# Sensor_PCI_Sch_V2.net
KiCad netlist of a schematic drawn in Altium Designer
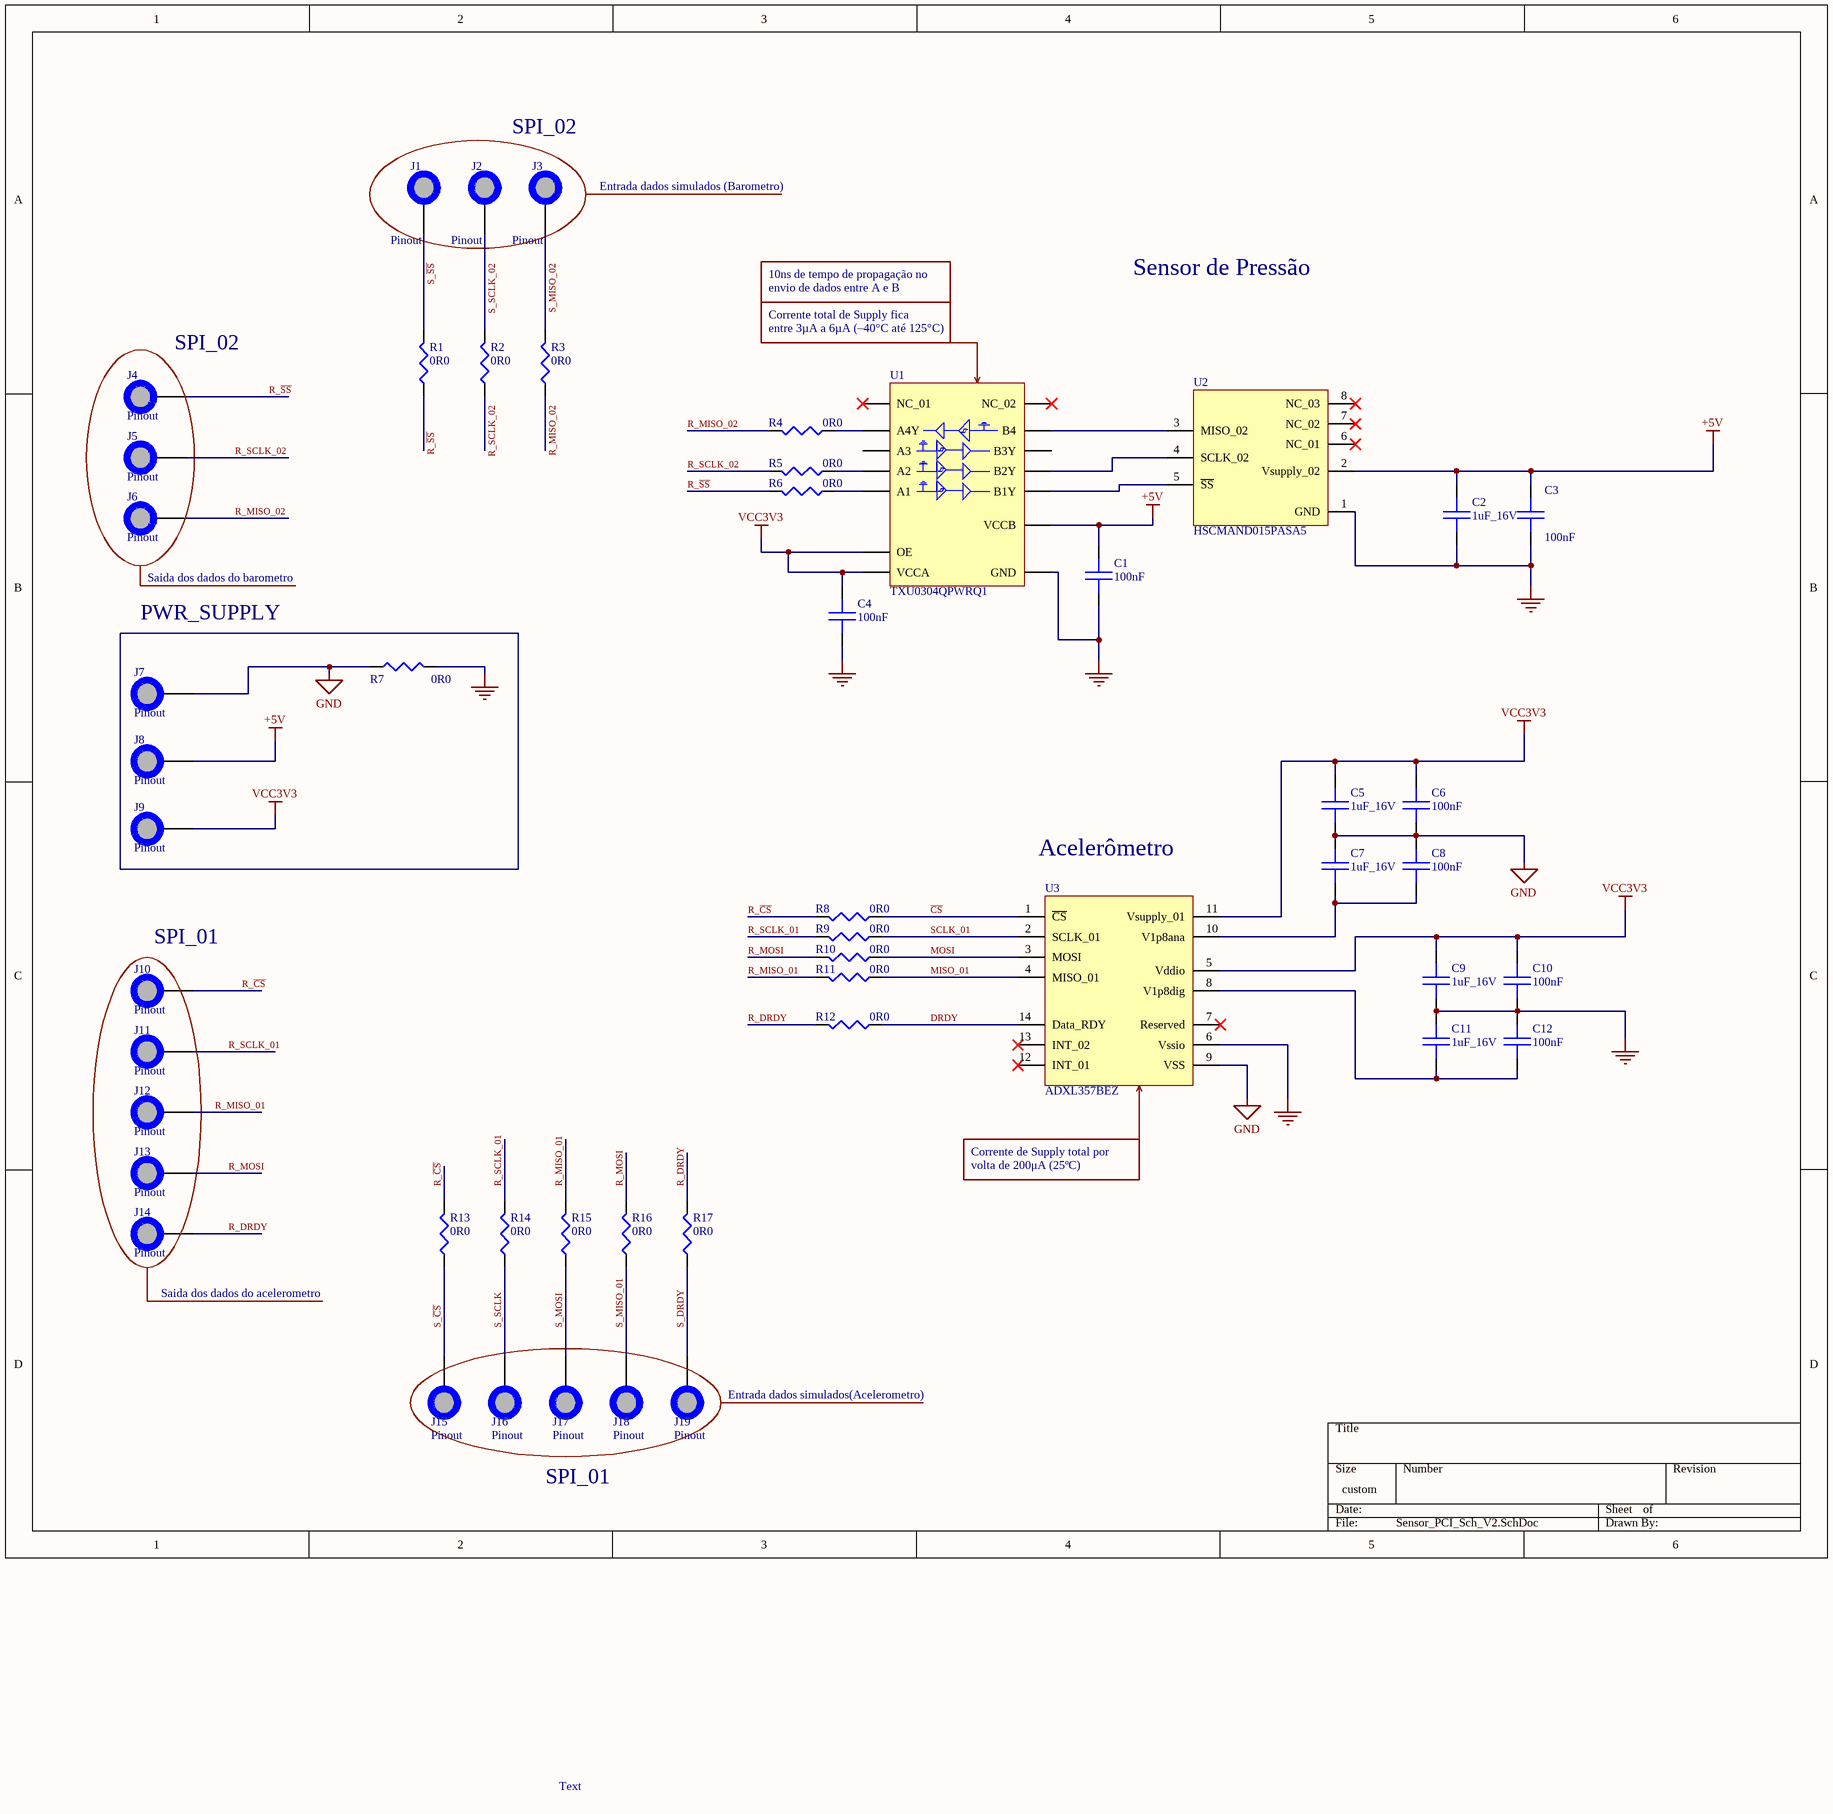
[diagram p0: Sensor_PCI_Sch_V2.SchDoc]

(export (version "E")
  (design (tool "Eeschema 10.0.6"))
  (components
    (comp (ref "C1")
      (value "100nF")
      (footprint "CP_0805")
      (description "Cap Ceramic 0.1uF 50V X7R 20% Pad SMD 0805 150°C T/R")
      (fields
        (field (name "MANUFACTURER") "Vishay Vitramon")
        (field (name "MANUFACTURER PART NUMBER") "VJ0805Y104MXAMR")
      )
      (libsource (lib "Sensor_PCI_schlib") (part "C_0805_0.1uF"))
    )
    (comp (ref "C2")
      (value "1uF_16V")
      (footprint "C_1206")
      (description "Cap Ceramic 1uF 16V Y5V 20% SMD 1206 85°C Plastic T/R")
      (fields
        (field (name "MANUFACTURER") "Vishay Vitramon")
        (field (name "MANUFACTURER PART NUMBER") "VJ1206V105MXJTW1BC")
      )
      (libsource (lib "Sensor_PCI_schlib") (part "C_1206_1uF_16V"))
    )
    (comp (ref "C3")
      (value "100nF")
      (footprint "CP_0805")
      (description "Cap Ceramic 0.1uF 50V X7R 20% Pad SMD 0805 150°C T/R")
      (fields
        (field (name "MANUFACTURER") "Vishay Vitramon")
        (field (name "MANUFACTURER PART NUMBER") "VJ0805Y104MXAMR")
      )
      (libsource (lib "Sensor_PCI_schlib") (part "C_0805_0.1uF"))
    )
    (comp (ref "C4")
      (value "100nF")
      (footprint "CP_0805")
      (description "Cap Ceramic 0.1uF 50V X7R 20% Pad SMD 0805 150°C T/R")
      (fields
        (field (name "MANUFACTURER") "Vishay Vitramon")
        (field (name "MANUFACTURER PART NUMBER") "VJ0805Y104MXAMR")
      )
      (libsource (lib "Sensor_PCI_schlib") (part "C_0805_0.1uF"))
    )
    (comp (ref "C5")
      (value "1uF_16V")
      (footprint "C_1206")
      (description "Cap Ceramic 1uF 16V Y5V 20% SMD 1206 85°C Plastic T/R")
      (fields
        (field (name "MANUFACTURER") "Vishay Vitramon")
        (field (name "MANUFACTURER PART NUMBER") "VJ1206V105MXJTW1BC")
      )
      (libsource (lib "Sensor_PCI_schlib") (part "C_1206_1uF_16V"))
    )
    (comp (ref "C6")
      (value "100nF")
      (footprint "CP_0805")
      (description "Cap Ceramic 0.1uF 50V X7R 20% Pad SMD 0805 150°C T/R")
      (fields
        (field (name "MANUFACTURER") "Vishay Vitramon")
        (field (name "MANUFACTURER PART NUMBER") "VJ0805Y104MXAMR")
      )
      (libsource (lib "Sensor_PCI_schlib") (part "C_0805_0.1uF"))
    )
    (comp (ref "C7")
      (value "1uF_16V")
      (footprint "C_1206")
      (description "Cap Ceramic 1uF 16V Y5V 20% SMD 1206 85°C Plastic T/R")
      (fields
        (field (name "MANUFACTURER") "Vishay Vitramon")
        (field (name "MANUFACTURER PART NUMBER") "VJ1206V105MXJTW1BC")
      )
      (libsource (lib "Sensor_PCI_schlib") (part "C_1206_1uF_16V"))
    )
    (comp (ref "C8")
      (value "100nF")
      (footprint "CP_0805")
      (description "Cap Ceramic 0.1uF 50V X7R 20% Pad SMD 0805 150°C T/R")
      (fields
        (field (name "MANUFACTURER") "Vishay Vitramon")
        (field (name "MANUFACTURER PART NUMBER") "VJ0805Y104MXAMR")
      )
      (libsource (lib "Sensor_PCI_schlib") (part "C_0805_0.1uF"))
    )
    (comp (ref "C9")
      (value "1uF_16V")
      (footprint "C_1206")
      (description "Cap Ceramic 1uF 16V Y5V 20% SMD 1206 85°C Plastic T/R")
      (fields
        (field (name "MANUFACTURER") "Vishay Vitramon")
        (field (name "MANUFACTURER PART NUMBER") "VJ1206V105MXJTW1BC")
      )
      (libsource (lib "Sensor_PCI_schlib") (part "C_1206_1uF_16V"))
    )
    (comp (ref "C10")
      (value "100nF")
      (footprint "CP_0805")
      (description "Cap Ceramic 0.1uF 50V X7R 20% Pad SMD 0805 150°C T/R")
      (fields
        (field (name "MANUFACTURER") "Vishay Vitramon")
        (field (name "MANUFACTURER PART NUMBER") "VJ0805Y104MXAMR")
      )
      (libsource (lib "Sensor_PCI_schlib") (part "C_0805_0.1uF"))
    )
    (comp (ref "C11")
      (value "1uF_16V")
      (footprint "C_1206")
      (description "Cap Ceramic 1uF 16V Y5V 20% SMD 1206 85°C Plastic T/R")
      (fields
        (field (name "MANUFACTURER") "Vishay Vitramon")
        (field (name "MANUFACTURER PART NUMBER") "VJ1206V105MXJTW1BC")
      )
      (libsource (lib "Sensor_PCI_schlib") (part "C_1206_1uF_16V"))
    )
    (comp (ref "C12")
      (value "100nF")
      (footprint "CP_0805")
      (description "Cap Ceramic 0.1uF 50V X7R 20% Pad SMD 0805 150°C T/R")
      (fields
        (field (name "MANUFACTURER") "Vishay Vitramon")
        (field (name "MANUFACTURER PART NUMBER") "VJ0805Y104MXAMR")
      )
      (libsource (lib "Sensor_PCI_schlib") (part "C_0805_0.1uF"))
    )
    (comp (ref "J1")
      (value "Pinout")
      (footprint "Pinout")
      (libsource (lib "Sensor_PCI_schlib") (part "Pinout"))
    )
    (comp (ref "J2")
      (value "Pinout")
      (footprint "Pinout")
      (libsource (lib "Sensor_PCI_schlib") (part "Pinout"))
    )
    (comp (ref "J3")
      (value "Pinout")
      (footprint "Pinout")
      (libsource (lib "Sensor_PCI_schlib") (part "Pinout"))
    )
    (comp (ref "J4")
      (value "Pinout")
      (footprint "Pinout")
      (libsource (lib "Sensor_PCI_schlib") (part "Pinout"))
    )
    (comp (ref "J5")
      (value "Pinout")
      (footprint "Pinout")
      (libsource (lib "Sensor_PCI_schlib") (part "Pinout"))
    )
    (comp (ref "J6")
      (value "Pinout")
      (footprint "Pinout")
      (libsource (lib "Sensor_PCI_schlib") (part "Pinout"))
    )
    (comp (ref "J7")
      (value "Pinout")
      (footprint "Pinout")
      (libsource (lib "Sensor_PCI_schlib") (part "Pinout"))
    )
    (comp (ref "J8")
      (value "Pinout")
      (footprint "Pinout")
      (libsource (lib "Sensor_PCI_schlib") (part "Pinout"))
    )
    (comp (ref "J9")
      (value "Pinout")
      (footprint "Pinout")
      (libsource (lib "Sensor_PCI_schlib") (part "Pinout"))
    )
    (comp (ref "J10")
      (value "Pinout")
      (footprint "Pinout")
      (libsource (lib "Sensor_PCI_schlib") (part "Pinout"))
    )
    (comp (ref "J11")
      (value "Pinout")
      (footprint "Pinout")
      (libsource (lib "Sensor_PCI_schlib") (part "Pinout"))
    )
    (comp (ref "J12")
      (value "Pinout")
      (footprint "Pinout")
      (libsource (lib "Sensor_PCI_schlib") (part "Pinout"))
    )
    (comp (ref "J13")
      (value "Pinout")
      (footprint "Pinout")
      (libsource (lib "Sensor_PCI_schlib") (part "Pinout"))
    )
    (comp (ref "J14")
      (value "Pinout")
      (footprint "Pinout")
      (libsource (lib "Sensor_PCI_schlib") (part "Pinout"))
    )
    (comp (ref "J15")
      (value "Pinout")
      (footprint "Pinout")
      (libsource (lib "Sensor_PCI_schlib") (part "Pinout"))
    )
    (comp (ref "J16")
      (value "Pinout")
      (footprint "Pinout")
      (libsource (lib "Sensor_PCI_schlib") (part "Pinout"))
    )
    (comp (ref "J17")
      (value "Pinout")
      (footprint "Pinout")
      (libsource (lib "Sensor_PCI_schlib") (part "Pinout"))
    )
    (comp (ref "J18")
      (value "Pinout")
      (footprint "Pinout")
      (libsource (lib "Sensor_PCI_schlib") (part "Pinout"))
    )
    (comp (ref "J19")
      (value "Pinout")
      (footprint "Pinout")
      (libsource (lib "Sensor_PCI_schlib") (part "Pinout"))
    )
    (comp (ref "R1")
      (value "0R0")
      (footprint "R_0805")
      (description "CRCW Thick Film Commodity Chip Resistor Jumper 0805 Size 0 Ohm 0.125 W 2-Pin SMD Paper T/R")
      (fields
        (field (name "MANUFACTURER") "Vishay Dale")
        (field (name "MANUFACTURER PART NUMBER") "CRCW08050000Z0ECC")
      )
      (libsource (lib "Sensor_PCI_schlib") (part "Res_0805_0R0"))
    )
    (comp (ref "R2")
      (value "0R0")
      (footprint "R_0805")
      (description "CRCW Thick Film Commodity Chip Resistor Jumper 0805 Size 0 Ohm 0.125 W 2-Pin SMD Paper T/R")
      (fields
        (field (name "MANUFACTURER") "Vishay Dale")
        (field (name "MANUFACTURER PART NUMBER") "CRCW08050000Z0ECC")
      )
      (libsource (lib "Sensor_PCI_schlib") (part "Res_0805_0R0"))
    )
    (comp (ref "R3")
      (value "0R0")
      (footprint "R_0805")
      (description "CRCW Thick Film Commodity Chip Resistor Jumper 0805 Size 0 Ohm 0.125 W 2-Pin SMD Paper T/R")
      (fields
        (field (name "MANUFACTURER") "Vishay Dale")
        (field (name "MANUFACTURER PART NUMBER") "CRCW08050000Z0ECC")
      )
      (libsource (lib "Sensor_PCI_schlib") (part "Res_0805_0R0"))
    )
    (comp (ref "R4")
      (value "0R0")
      (footprint "R_0805")
      (description "CRCW Thick Film Commodity Chip Resistor Jumper 0805 Size 0 Ohm 0.125 W 2-Pin SMD Paper T/R")
      (fields
        (field (name "MANUFACTURER") "Vishay Dale")
        (field (name "MANUFACTURER PART NUMBER") "CRCW08050000Z0ECC")
      )
      (libsource (lib "Sensor_PCI_schlib") (part "Res_0805_0R0"))
    )
    (comp (ref "R5")
      (value "0R0")
      (footprint "R_0805")
      (description "CRCW Thick Film Commodity Chip Resistor Jumper 0805 Size 0 Ohm 0.125 W 2-Pin SMD Paper T/R")
      (fields
        (field (name "MANUFACTURER") "Vishay Dale")
        (field (name "MANUFACTURER PART NUMBER") "CRCW08050000Z0ECC")
      )
      (libsource (lib "Sensor_PCI_schlib") (part "Res_0805_0R0"))
    )
    (comp (ref "R6")
      (value "0R0")
      (footprint "R_0805")
      (description "CRCW Thick Film Commodity Chip Resistor Jumper 0805 Size 0 Ohm 0.125 W 2-Pin SMD Paper T/R")
      (fields
        (field (name "MANUFACTURER") "Vishay Dale")
        (field (name "MANUFACTURER PART NUMBER") "CRCW08050000Z0ECC")
      )
      (libsource (lib "Sensor_PCI_schlib") (part "Res_0805_0R0"))
    )
    (comp (ref "R7")
      (value "0R0")
      (footprint "R_0805")
      (description "CRCW Thick Film Commodity Chip Resistor Jumper 0805 Size 0 Ohm 0.125 W 2-Pin SMD Paper T/R")
      (fields
        (field (name "MANUFACTURER") "Vishay Dale")
        (field (name "MANUFACTURER PART NUMBER") "CRCW08050000Z0ECC")
      )
      (libsource (lib "Sensor_PCI_schlib") (part "Res_0805_0R0"))
    )
    (comp (ref "R8")
      (value "0R0")
      (footprint "R_0805")
      (description "CRCW Thick Film Commodity Chip Resistor Jumper 0805 Size 0 Ohm 0.125 W 2-Pin SMD Paper T/R")
      (fields
        (field (name "MANUFACTURER") "Vishay Dale")
        (field (name "MANUFACTURER PART NUMBER") "CRCW08050000Z0ECC")
      )
      (libsource (lib "Sensor_PCI_schlib") (part "Res_0805_0R0"))
    )
    (comp (ref "R9")
      (value "0R0")
      (footprint "R_0805")
      (description "CRCW Thick Film Commodity Chip Resistor Jumper 0805 Size 0 Ohm 0.125 W 2-Pin SMD Paper T/R")
      (fields
        (field (name "MANUFACTURER") "Vishay Dale")
        (field (name "MANUFACTURER PART NUMBER") "CRCW08050000Z0ECC")
      )
      (libsource (lib "Sensor_PCI_schlib") (part "Res_0805_0R0"))
    )
    (comp (ref "R10")
      (value "0R0")
      (footprint "R_0805")
      (description "CRCW Thick Film Commodity Chip Resistor Jumper 0805 Size 0 Ohm 0.125 W 2-Pin SMD Paper T/R")
      (fields
        (field (name "MANUFACTURER") "Vishay Dale")
        (field (name "MANUFACTURER PART NUMBER") "CRCW08050000Z0ECC")
      )
      (libsource (lib "Sensor_PCI_schlib") (part "Res_0805_0R0"))
    )
    (comp (ref "R11")
      (value "0R0")
      (footprint "R_0805")
      (description "CRCW Thick Film Commodity Chip Resistor Jumper 0805 Size 0 Ohm 0.125 W 2-Pin SMD Paper T/R")
      (fields
        (field (name "MANUFACTURER") "Vishay Dale")
        (field (name "MANUFACTURER PART NUMBER") "CRCW08050000Z0ECC")
      )
      (libsource (lib "Sensor_PCI_schlib") (part "Res_0805_0R0"))
    )
    (comp (ref "R12")
      (value "0R0")
      (footprint "R_0805")
      (description "CRCW Thick Film Commodity Chip Resistor Jumper 0805 Size 0 Ohm 0.125 W 2-Pin SMD Paper T/R")
      (fields
        (field (name "MANUFACTURER") "Vishay Dale")
        (field (name "MANUFACTURER PART NUMBER") "CRCW08050000Z0ECC")
      )
      (libsource (lib "Sensor_PCI_schlib") (part "Res_0805_0R0"))
    )
    (comp (ref "R13")
      (value "0R0")
      (footprint "R_0805")
      (description "CRCW Thick Film Commodity Chip Resistor Jumper 0805 Size 0 Ohm 0.125 W 2-Pin SMD Paper T/R")
      (fields
        (field (name "MANUFACTURER") "Vishay Dale")
        (field (name "MANUFACTURER PART NUMBER") "CRCW08050000Z0ECC")
      )
      (libsource (lib "Sensor_PCI_schlib") (part "Res_0805_0R0"))
    )
    (comp (ref "R14")
      (value "0R0")
      (footprint "R_0805")
      (description "CRCW Thick Film Commodity Chip Resistor Jumper 0805 Size 0 Ohm 0.125 W 2-Pin SMD Paper T/R")
      (fields
        (field (name "MANUFACTURER") "Vishay Dale")
        (field (name "MANUFACTURER PART NUMBER") "CRCW08050000Z0ECC")
      )
      (libsource (lib "Sensor_PCI_schlib") (part "Res_0805_0R0"))
    )
    (comp (ref "R15")
      (value "0R0")
      (footprint "R_0805")
      (description "CRCW Thick Film Commodity Chip Resistor Jumper 0805 Size 0 Ohm 0.125 W 2-Pin SMD Paper T/R")
      (fields
        (field (name "MANUFACTURER") "Vishay Dale")
        (field (name "MANUFACTURER PART NUMBER") "CRCW08050000Z0ECC")
      )
      (libsource (lib "Sensor_PCI_schlib") (part "Res_0805_0R0"))
    )
    (comp (ref "R16")
      (value "0R0")
      (footprint "R_0805")
      (description "CRCW Thick Film Commodity Chip Resistor Jumper 0805 Size 0 Ohm 0.125 W 2-Pin SMD Paper T/R")
      (fields
        (field (name "MANUFACTURER") "Vishay Dale")
        (field (name "MANUFACTURER PART NUMBER") "CRCW08050000Z0ECC")
      )
      (libsource (lib "Sensor_PCI_schlib") (part "Res_0805_0R0"))
    )
    (comp (ref "R17")
      (value "0R0")
      (footprint "R_0805")
      (description "CRCW Thick Film Commodity Chip Resistor Jumper 0805 Size 0 Ohm 0.125 W 2-Pin SMD Paper T/R")
      (fields
        (field (name "MANUFACTURER") "Vishay Dale")
        (field (name "MANUFACTURER PART NUMBER") "CRCW08050000Z0ECC")
      )
      (libsource (lib "Sensor_PCI_schlib") (part "Res_0805_0R0"))
    )
    (comp (ref "U1")
      (value "TXU0304QPWRQ1")
      (footprint "TSSOP-PW")
      (description "Automotive four channel unidirectional level shifter 14-TSSOP -40 to 125")
      (fields (field (name "MANUFACTURER") "Texas Instruments"))
      (libsource (lib "Sensor_PCI_schlib") (part "Tradutor fixo de Tensão-SPI"))
    )
    (comp (ref "U2")
      (value "HSCMAND015PASA5")
      (footprint "SMT_08_2.54mm")
      (description "Board Mount Pressure Sensors SMT, Single Ax Barbed Absolute, 5V")
      (fields (field (name "MANUFACTURER") "Honeywell Sensing & Control"))
      (libsource (lib "Sensor_PCI_schlib") (part "Sensor_Pressão"))
    )
    (comp (ref "U3")
      (value "ADXL357BEZ")
      (footprint "Quad_14_1.2mm")
      (description "Accelerometer Tri-axis Digital Accel")
      (fields (field (name "MANUFACTURER") "Analog Devices"))
      (libsource (lib "Sensor_PCI_schlib") (part "Acelerômetro"))
    )
  )
  (nets
    (net (code "1") (name "+5V") (class "Default")
      (node (ref "C1") (pin "2") (pinfunction "2_2") (pintype "passive"))
      (node (ref "C2") (pin "1") (pinfunction "3_1") (pintype "passive"))
      (node (ref "C3") (pin "2") (pinfunction "2_2") (pintype "passive"))
      (node (ref "J8") (pin "1") (pinfunction "1_1") (pintype "passive"))
      (node (ref "U1") (pin "14") (pinfunction "VCCB_14") (pintype "passive"))
      (node (ref "U2") (pin "2") (pinfunction "Vsupply_02_2") (pintype "passive"))
    )
    (net (code "2") (name "/DRDY") (class "Default")
      (node (ref "R12") (pin "1") (pinfunction "1_1") (pintype "passive"))
      (node (ref "U3") (pin "14") (pinfunction "Data_RDY_14") (pintype "passive"))
    )
    (net (code "3") (name "/MISO_01") (class "Default")
      (node (ref "R11") (pin "1") (pinfunction "1_1") (pintype "passive"))
      (node (ref "U3") (pin "4") (pinfunction "MISO_01_4") (pintype "passive"))
    )
    (net (code "4") (name "/MOSI") (class "Default")
      (node (ref "R10") (pin "1") (pinfunction "1_1") (pintype "passive"))
      (node (ref "U3") (pin "3") (pinfunction "MOSI_3") (pintype "passive"))
    )
    (net (code "5") (name "/R_DRDY") (class "Default")
      (node (ref "J14") (pin "1") (pinfunction "1_1") (pintype "passive"))
      (node (ref "R12") (pin "2") (pinfunction "2_2") (pintype "passive"))
      (node (ref "R17") (pin "2") (pinfunction "2_2") (pintype "passive"))
    )
    (net (code "6") (name "/R_MISO_01") (class "Default")
      (node (ref "J12") (pin "1") (pinfunction "1_1") (pintype "passive"))
      (node (ref "R11") (pin "2") (pinfunction "2_2") (pintype "passive"))
      (node (ref "R15") (pin "2") (pinfunction "2_2") (pintype "passive"))
    )
    (net (code "7") (name "/R_MISO_02") (class "Default")
      (node (ref "J6") (pin "1") (pinfunction "1_1") (pintype "passive"))
      (node (ref "R3") (pin "1") (pinfunction "1_1") (pintype "passive"))
      (node (ref "R4") (pin "2") (pinfunction "2_2") (pintype "passive"))
    )
    (net (code "8") (name "/R_MOSI") (class "Default")
      (node (ref "J13") (pin "1") (pinfunction "1_1") (pintype "passive"))
      (node (ref "R10") (pin "2") (pinfunction "2_2") (pintype "passive"))
      (node (ref "R16") (pin "2") (pinfunction "2_2") (pintype "passive"))
    )
    (net (code "9") (name "/R_SCLK_01") (class "Default")
      (node (ref "J11") (pin "1") (pinfunction "1_1") (pintype "passive"))
      (node (ref "R14") (pin "2") (pinfunction "2_2") (pintype "passive"))
      (node (ref "R9") (pin "2") (pinfunction "2_2") (pintype "passive"))
    )
    (net (code "10") (name "/R_SCLK_02") (class "Default")
      (node (ref "J5") (pin "1") (pinfunction "1_1") (pintype "passive"))
      (node (ref "R2") (pin "1") (pinfunction "1_1") (pintype "passive"))
      (node (ref "R5") (pin "2") (pinfunction "2_2") (pintype "passive"))
    )
    (net (code "11") (name "/R_~{CS}") (class "Default")
      (node (ref "J10") (pin "1") (pinfunction "1_1") (pintype "passive"))
      (node (ref "R13") (pin "2") (pinfunction "2_2") (pintype "passive"))
      (node (ref "R8") (pin "2") (pinfunction "2_2") (pintype "passive"))
    )
    (net (code "12") (name "/R_~{SS}") (class "Default")
      (node (ref "J4") (pin "1") (pinfunction "1_1") (pintype "passive"))
      (node (ref "R1") (pin "1") (pinfunction "1_1") (pintype "passive"))
      (node (ref "R6") (pin "2") (pinfunction "2_2") (pintype "passive"))
    )
    (net (code "13") (name "/SCLK_01") (class "Default")
      (node (ref "R9") (pin "1") (pinfunction "1_1") (pintype "passive"))
      (node (ref "U3") (pin "2") (pinfunction "SCLK_01_2") (pintype "passive"))
    )
    (net (code "14") (name "/S_DRDY") (class "Default")
      (node (ref "J19") (pin "1") (pinfunction "1_1") (pintype "passive"))
      (node (ref "R17") (pin "1") (pinfunction "1_1") (pintype "passive"))
    )
    (net (code "15") (name "/S_MISO_01") (class "Default")
      (node (ref "J18") (pin "1") (pinfunction "1_1") (pintype "passive"))
      (node (ref "R16") (pin "1") (pinfunction "1_1") (pintype "passive"))
    )
    (net (code "16") (name "/S_MISO_02") (class "Default")
      (node (ref "J3") (pin "1") (pinfunction "1_1") (pintype "passive"))
      (node (ref "R3") (pin "2") (pinfunction "2_2") (pintype "passive"))
    )
    (net (code "17") (name "/S_MOSI") (class "Default")
      (node (ref "J17") (pin "1") (pinfunction "1_1") (pintype "passive"))
      (node (ref "R15") (pin "1") (pinfunction "1_1") (pintype "passive"))
    )
    (net (code "18") (name "/S_SCLK") (class "Default")
      (node (ref "J16") (pin "1") (pinfunction "1_1") (pintype "passive"))
      (node (ref "R14") (pin "1") (pinfunction "1_1") (pintype "passive"))
    )
    (net (code "19") (name "/S_SCLK_02") (class "Default")
      (node (ref "J2") (pin "1") (pinfunction "1_1") (pintype "passive"))
      (node (ref "R2") (pin "2") (pinfunction "2_2") (pintype "passive"))
    )
    (net (code "20") (name "/S_~{CS}") (class "Default")
      (node (ref "J15") (pin "1") (pinfunction "1_1") (pintype "passive"))
      (node (ref "R13") (pin "1") (pinfunction "1_1") (pintype "passive"))
    )
    (net (code "21") (name "/S_~{SS}") (class "Default")
      (node (ref "J1") (pin "1") (pinfunction "1_1") (pintype "passive"))
      (node (ref "R1") (pin "2") (pinfunction "2_2") (pintype "passive"))
    )
    (net (code "22") (name "/~{CS}") (class "Default")
      (node (ref "R8") (pin "1") (pinfunction "1_1") (pintype "passive"))
      (node (ref "U3") (pin "1") (pinfunction "~{CS}_1") (pintype "passive"))
    )
    (net (code "23") (name "GND") (class "Default")
      (node (ref "C1") (pin "1") (pinfunction "1_1") (pintype "passive"))
      (node (ref "C10") (pin "1") (pinfunction "1_1") (pintype "passive"))
      (node (ref "C11") (pin "1") (pinfunction "3_1") (pintype "passive"))
      (node (ref "C12") (pin "2") (pinfunction "2_2") (pintype "passive"))
      (node (ref "C2") (pin "2") (pinfunction "4_2") (pintype "passive"))
      (node (ref "C3") (pin "1") (pinfunction "1_1") (pintype "passive"))
      (node (ref "C4") (pin "1") (pinfunction "1_1") (pintype "passive"))
      (node (ref "C5") (pin "2") (pinfunction "4_2") (pintype "passive"))
      (node (ref "C6") (pin "1") (pinfunction "1_1") (pintype "passive"))
      (node (ref "C7") (pin "1") (pinfunction "3_1") (pintype "passive"))
      (node (ref "C8") (pin "2") (pinfunction "2_2") (pintype "passive"))
      (node (ref "C9") (pin "2") (pinfunction "4_2") (pintype "passive"))
      (node (ref "J7") (pin "1") (pinfunction "1_1") (pintype "passive"))
      (node (ref "R7") (pin "1") (pinfunction "1_1") (pintype "passive"))
      (node (ref "R7") (pin "2") (pinfunction "2_2") (pintype "passive"))
      (node (ref "U1") (pin "7") (pinfunction "GND_7") (pintype "passive"))
      (node (ref "U2") (pin "1") (pinfunction "GND_1") (pintype "passive"))
      (node (ref "U3") (pin "6") (pinfunction "Vssio_6") (pintype "passive"))
      (node (ref "U3") (pin "9") (pinfunction "VSS_9") (pintype "passive"))
    )
    (net (code "24") (name "Net-(C7-4)") (class "Default")
      (node (ref "C7") (pin "2") (pinfunction "4_2") (pintype "passive"))
      (node (ref "C8") (pin "1") (pinfunction "1_1") (pintype "passive"))
      (node (ref "U3") (pin "10") (pinfunction "V1p8ana_10") (pintype "passive"))
    )
    (net (code "25") (name "Net-(C11-4)") (class "Default")
      (node (ref "C11") (pin "2") (pinfunction "4_2") (pintype "passive"))
      (node (ref "C12") (pin "1") (pinfunction "1_1") (pintype "passive"))
      (node (ref "U3") (pin "8") (pinfunction "V1p8dig_8") (pintype "passive"))
    )
    (net (code "26") (name "Net-(U1-A1)") (class "Default")
      (node (ref "R6") (pin "1") (pinfunction "1_1") (pintype "passive"))
      (node (ref "U1") (pin "2") (pinfunction "A1_2") (pintype "passive"))
    )
    (net (code "27") (name "Net-(U1-A2)") (class "Default")
      (node (ref "R5") (pin "1") (pinfunction "1_1") (pintype "passive"))
      (node (ref "U1") (pin "3") (pinfunction "A2_3") (pintype "passive"))
    )
    (net (code "28") (name "Net-(U1-A4Y)") (class "Default")
      (node (ref "R4") (pin "1") (pinfunction "1_1") (pintype "passive"))
      (node (ref "U1") (pin "5") (pinfunction "A4Y_5") (pintype "passive"))
    )
    (net (code "29") (name "Net-(U1-B1Y)") (class "Default")
      (node (ref "U1") (pin "13") (pinfunction "B1Y_13") (pintype "passive"))
      (node (ref "U2") (pin "5") (pinfunction "~{SS}_5") (pintype "passive"))
    )
    (net (code "30") (name "Net-(U1-B2Y)") (class "Default")
      (node (ref "U1") (pin "12") (pinfunction "B2Y_12") (pintype "passive"))
      (node (ref "U2") (pin "4") (pinfunction "SCLK_02_4") (pintype "passive"))
    )
    (net (code "31") (name "Net-(U1-B4)") (class "Default")
      (node (ref "U1") (pin "10") (pinfunction "B4_10") (pintype "passive"))
      (node (ref "U2") (pin "3") (pinfunction "MISO_02_3") (pintype "passive"))
    )
    (net (code "32") (name "VCC3V3") (class "Default")
      (node (ref "C10") (pin "2") (pinfunction "2_2") (pintype "passive"))
      (node (ref "C4") (pin "2") (pinfunction "2_2") (pintype "passive"))
      (node (ref "C5") (pin "1") (pinfunction "3_1") (pintype "passive"))
      (node (ref "C6") (pin "2") (pinfunction "2_2") (pintype "passive"))
      (node (ref "C9") (pin "1") (pinfunction "3_1") (pintype "passive"))
      (node (ref "J9") (pin "1") (pinfunction "1_1") (pintype "passive"))
      (node (ref "U1") (pin "1") (pinfunction "VCCA_1") (pintype "passive"))
      (node (ref "U1") (pin "8") (pinfunction "OE_8") (pintype "passive"))
      (node (ref "U3") (pin "11") (pinfunction "Vsupply_01_11") (pintype "passive"))
      (node (ref "U3") (pin "5") (pinfunction "Vddio_5") (pintype "passive"))
    )
    (net (code "33") (name "unconnected-(U1-A3-Pad4)") (class "Default")
      (node (ref "U1") (pin "4") (pinfunction "A3_4") (pintype "passive"))
    )
    (net (code "34") (name "unconnected-(U1-B3Y-Pad11)") (class "Default")
      (node (ref "U1") (pin "11") (pinfunction "B3Y_11") (pintype "passive"))
    )
    (net (code "35") (name "unconnected-(U1-NC_01-Pad6)") (class "Default")
      (node (ref "U1") (pin "6") (pinfunction "NC_01_6") (pintype "passive+no_connect"))
    )
    (net (code "36") (name "unconnected-(U1-NC_02-Pad9)") (class "Default")
      (node (ref "U1") (pin "9") (pinfunction "NC_02_9") (pintype "passive+no_connect"))
    )
    (net (code "37") (name "unconnected-(U2-NC_01-Pad6)") (class "Default")
      (node (ref "U2") (pin "6") (pinfunction "NC_01_6") (pintype "passive+no_connect"))
    )
    (net (code "38") (name "unconnected-(U2-NC_02-Pad7)") (class "Default")
      (node (ref "U2") (pin "7") (pinfunction "NC_02_7") (pintype "passive+no_connect"))
    )
    (net (code "39") (name "unconnected-(U2-NC_03-Pad8)") (class "Default")
      (node (ref "U2") (pin "8") (pinfunction "NC_03_8") (pintype "passive+no_connect"))
    )
    (net (code "40") (name "unconnected-(U3-INT_01-Pad12)") (class "Default")
      (node (ref "U3") (pin "12") (pinfunction "INT_01_12") (pintype "passive+no_connect"))
    )
    (net (code "41") (name "unconnected-(U3-INT_02-Pad13)") (class "Default")
      (node (ref "U3") (pin "13") (pinfunction "INT_02_13") (pintype "passive+no_connect"))
    )
    (net (code "42") (name "unconnected-(U3-Reserved-Pad7)") (class "Default")
      (node (ref "U3") (pin "7") (pinfunction "Reserved_7") (pintype "passive+no_connect"))
    )
  )
)
